# BSPD_v8.net
KiCad netlist of a schematic drawn in EAGLE
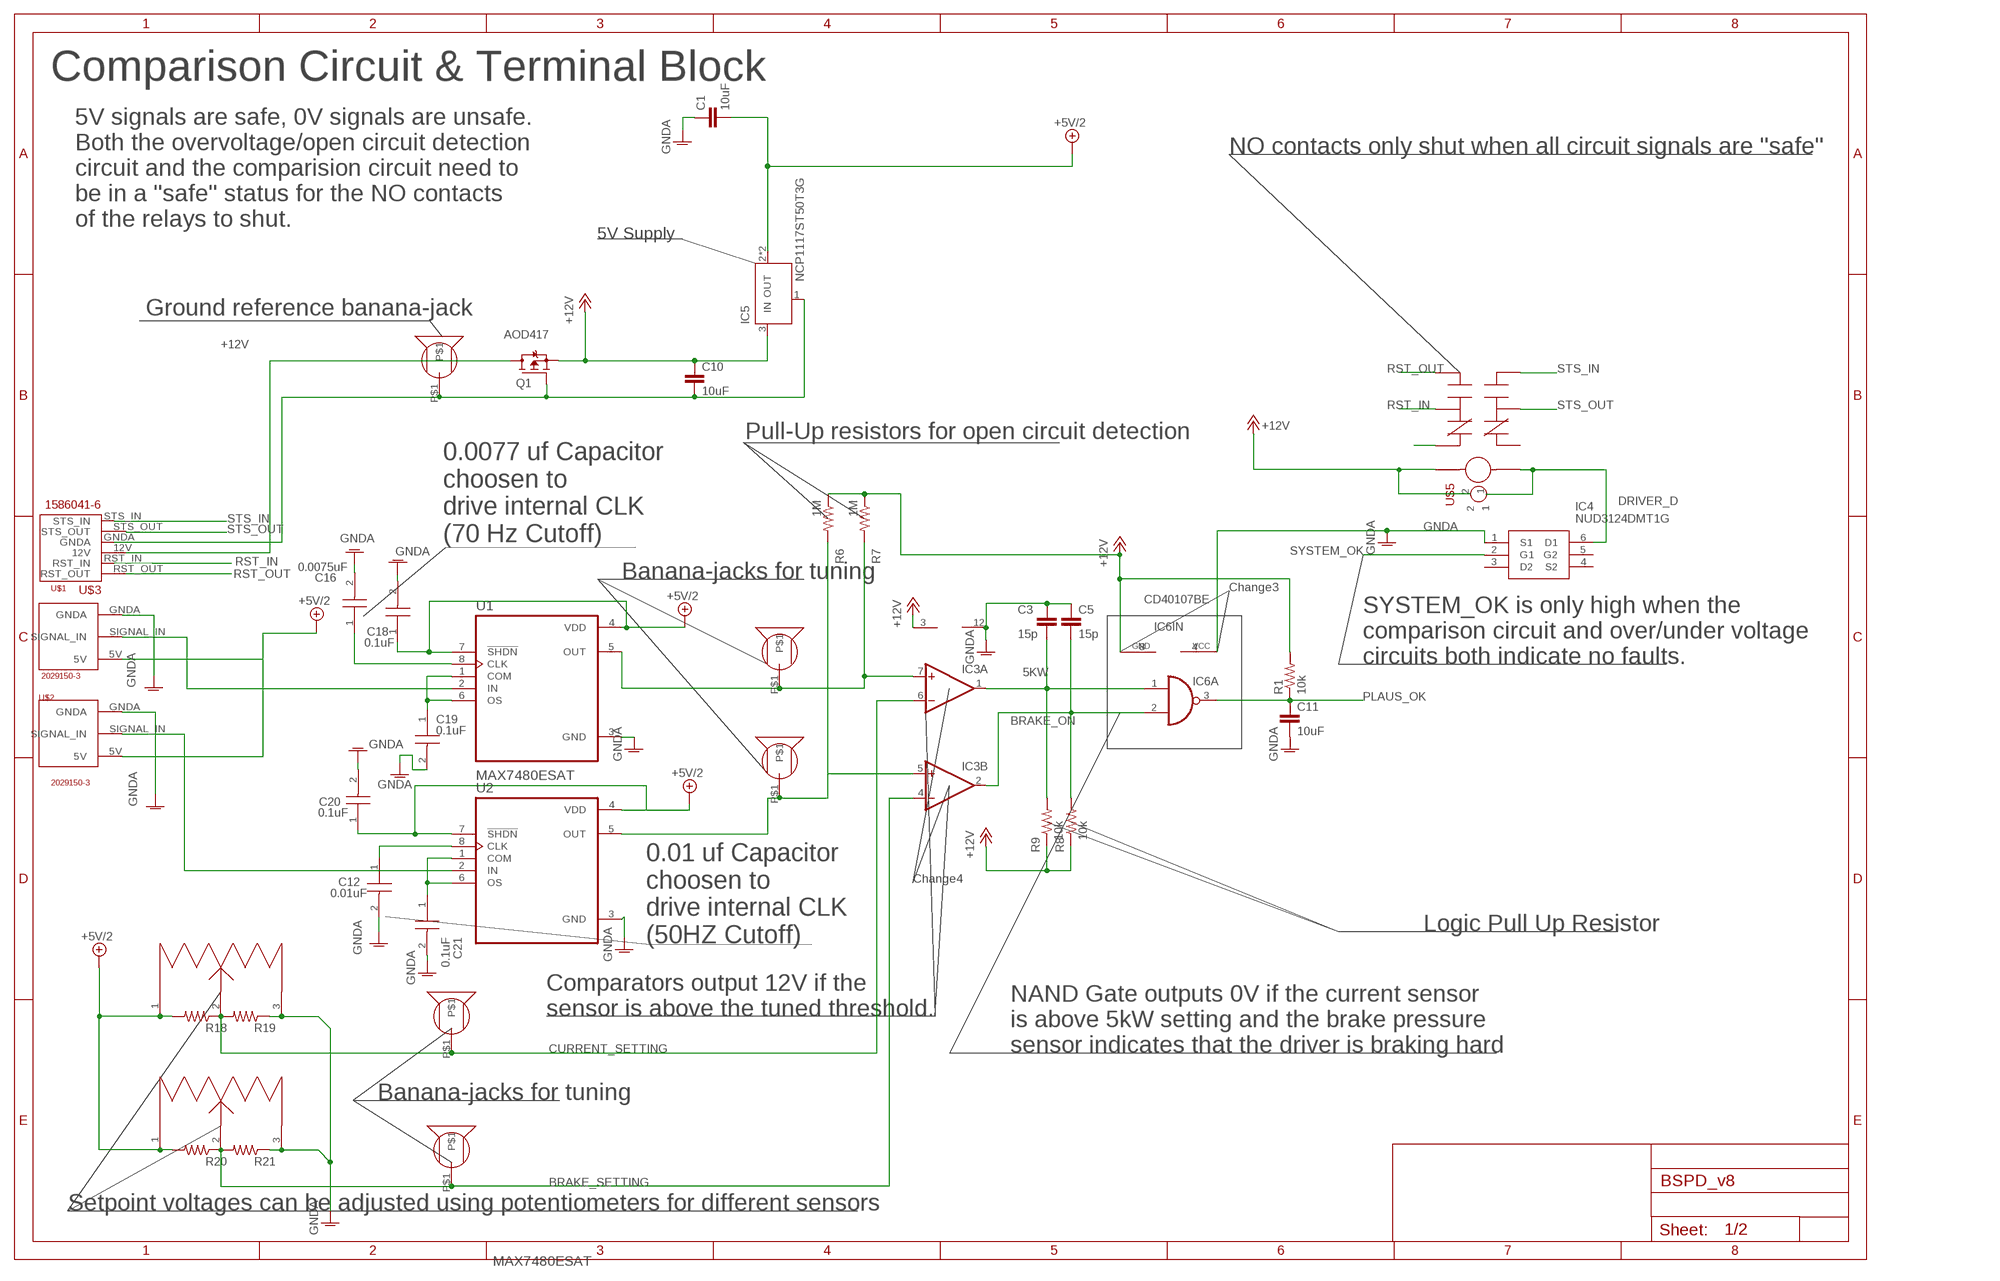
[diagram p0: schematic, sheet 1]
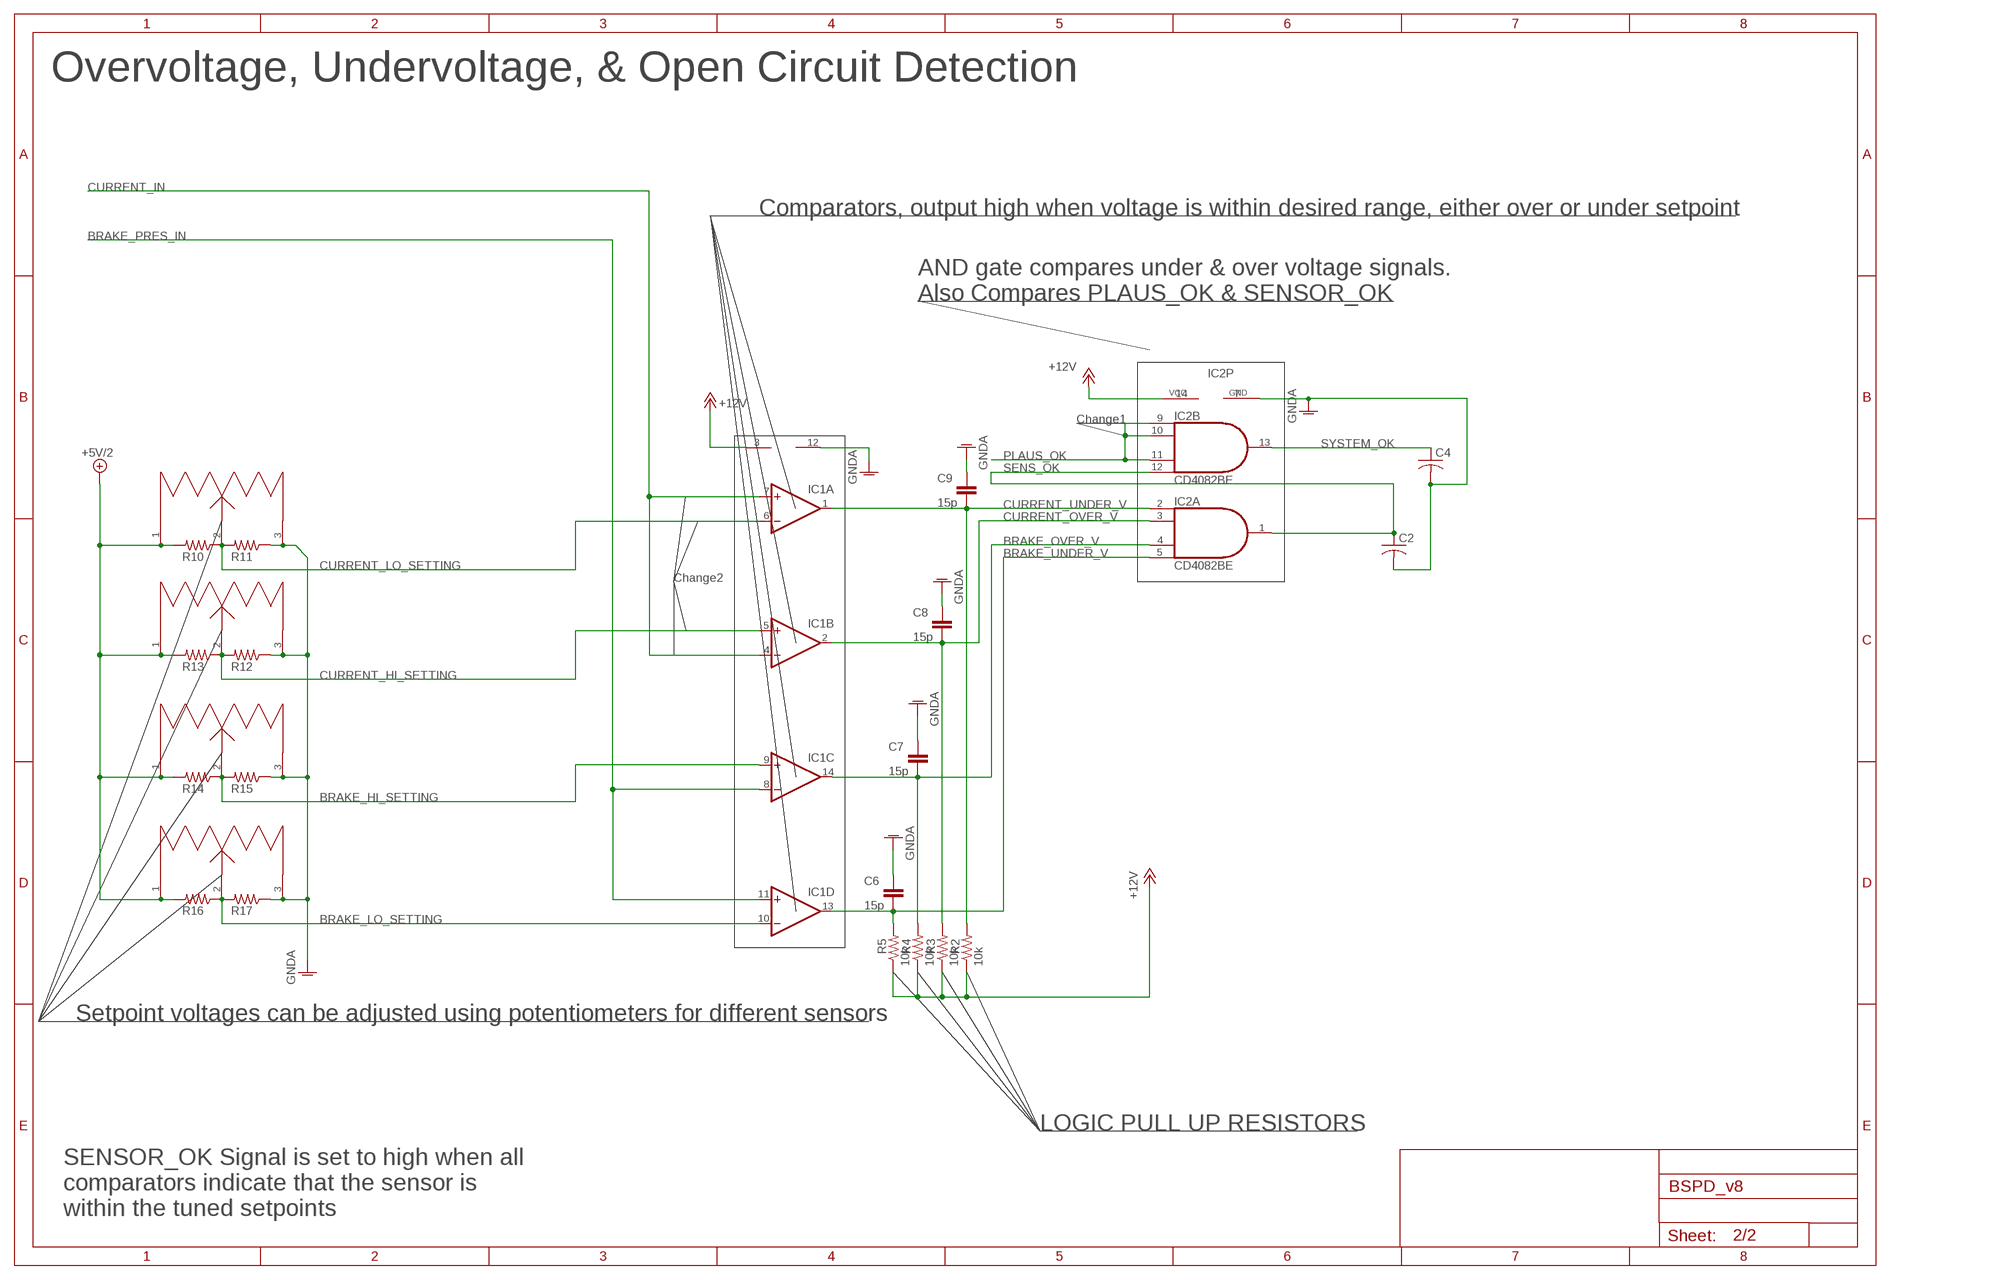
[diagram p1: schematic, sheet 2]

(export (version "E")
  (design (tool "Eeschema 10.0.6"))
  (components
    (comp (ref "C1")
      (value "10uF")
      (footprint "eagle-import:C0805")
      (libsource (lib "eagle-import") (part "resistor_348_C-EUC0805"))
    )
    (comp (ref "C3")
      (value "15p")
      (footprint "eagle-import:C0805")
      (libsource (lib "eagle-import") (part "C-EUC0805"))
    )
    (comp (ref "C5")
      (value "15p")
      (footprint "eagle-import:C0805")
      (libsource (lib "eagle-import") (part "C-EUC0805"))
    )
    (comp (ref "C10")
      (value "10uF")
      (footprint "eagle-import:C0805")
      (libsource (lib "eagle-import") (part "resistor_348_C-EUC0805"))
    )
    (comp (ref "C11")
      (value "10uF")
      (footprint "eagle-import:C0805")
      (libsource (lib "eagle-import") (part "resistor_348_C-EUC0805"))
    )
    (comp (ref "C12")
      (value "0.01uF")
      (footprint "eagle-import:CAPC2012X95N")
      (fields
        (field (name "MANUFACTURER_PART_NUMBER") "GRM2195C1H103JA01D")
        (field (name "MOUSER_PART_NUMBER") "81-GRM215C1H103JA01D")
      )
      (libsource (lib "eagle-import") (part "GRM2195C1H103JA01D"))
    )
    (comp (ref "C16")
      (value "0.0075uF")
      (footprint "eagle-import:CAPC2012X95N")
      (fields
        (field (name "MANUFACTURER_PART_NUMBER") "GRM2195C1H752JA01D")
        (field (name "MOUSER_PART_NUMBER") "81-GRM2195C1H752JA1D")
      )
      (libsource (lib "eagle-import") (part "GRM2195C1H752JA01D"))
    )
    (comp (ref "C18")
      (value "0.1uF")
      (footprint "eagle-import:CAPC2012X140N")
      (fields
        (field (name "MANUFACTURER_PART_NUMBER") "GCM21BR72A104KA37L")
        (field (name "MOUSER_PART_NUMBER") "81-GCM21BR72A104KA7L")
      )
      (libsource (lib "eagle-import") (part "GCM21BR72A104KA37L"))
    )
    (comp (ref "C19")
      (value "0.1uF")
      (footprint "eagle-import:CAPC2012X140N")
      (fields
        (field (name "MANUFACTURER_PART_NUMBER") "GCM21BR72A104KA37L")
        (field (name "MOUSER_PART_NUMBER") "81-GCM21BR72A104KA7L")
      )
      (libsource (lib "eagle-import") (part "GCM21BR72A104KA37L"))
    )
    (comp (ref "C20")
      (value "0.1uF")
      (footprint "eagle-import:CAPC2012X140N")
      (fields
        (field (name "MANUFACTURER_PART_NUMBER") "GCM21BR72A104KA37L")
        (field (name "MOUSER_PART_NUMBER") "81-GCM21BR72A104KA7L")
      )
      (libsource (lib "eagle-import") (part "GCM21BR72A104KA37L"))
    )
    (comp (ref "C21")
      (value "0.1uF")
      (footprint "eagle-import:CAPC2012X140N")
      (fields
        (field (name "MANUFACTURER_PART_NUMBER") "GCM21BR72A104KA37L")
        (field (name "MOUSER_PART_NUMBER") "81-GCM21BR72A104KA7L")
      )
      (libsource (lib "eagle-import") (part "GCM21BR72A104KA37L"))
    )
    (comp (ref "IC3")
      (value "4AMP_P11+7N")
      (footprint "eagle-import:DIL14")
      (libsource (lib "eagle-import") (part "4AMP_P11+7N"))
    )
    (comp (ref "IC4")
      (value "NUD3124DMT1G")
      (footprint "eagle-import:SOT95P275X110-6N")
      (fields (field (name "MOUSER_PART_NUMBER") "863-NUD3124DMT1G"))
      (libsource (lib "eagle-import") (part "NUD3124DMT1G"))
    )
    (comp (ref "IC5")
      (value "NCP1117ST50T3G")
      (footprint "eagle-import:SOT223")
      (libsource (lib "eagle-import") (part "NCP1117ST50T3G"))
    )
    (comp (ref "IC6")
      (value "CD40107BE")
      (footprint "eagle-import:DIL08")
      (libsource (lib "eagle-import") (part "CD40107BE"))
    )
    (comp (ref "Q1")
      (value "AOD417")
      (footprint "eagle-import:TO252")
      (fields (field (name "MF") "ON Semiconductor") (field (name "MP") "FDD4141"))
      (libsource (lib "eagle-import") (part "FDD4141TO252"))
    )
    (comp (ref "R1")
      (value "10k")
      (footprint "eagle-import:M0805")
      (libsource (lib "eagle-import") (part "R-US_M0805"))
    )
    (comp (ref "R6")
      (value "1M")
      (footprint "eagle-import:M0805")
      (libsource (lib "eagle-import") (part "resistor_R-US_M0805"))
    )
    (comp (ref "R7")
      (value "1M")
      (footprint "eagle-import:M0805")
      (libsource (lib "eagle-import") (part "resistor_R-US_M0805"))
    )
    (comp (ref "R8")
      (value "10k")
      (footprint "eagle-import:M0805")
      (libsource (lib "eagle-import") (part "resistor_R-US_M0805"))
    )
    (comp (ref "R9")
      (value "10k")
      (footprint "eagle-import:M0805")
      (libsource (lib "eagle-import") (part "resistor_R-US_M0805"))
    )
    (comp (ref "R18")
      (value "R-US_M0805")
      (footprint "eagle-import:M0805")
      (libsource (lib "eagle-import") (part "resistor_R-US_M0805"))
    )
    (comp (ref "R19")
      (value "R-US_M0805")
      (footprint "eagle-import:M0805")
      (libsource (lib "eagle-import") (part "resistor_R-US_M0805"))
    )
    (comp (ref "R20")
      (value "R-US_M0805")
      (footprint "eagle-import:M0805")
      (libsource (lib "eagle-import") (part "resistor_R-US_M0805"))
    )
    (comp (ref "R21")
      (value "R-US_M0805")
      (footprint "eagle-import:M0805")
      (libsource (lib "eagle-import") (part "resistor_R-US_M0805"))
    )
    (comp (ref "U$1")
      (value "2029150-3")
      (footprint "eagle-import:2029150-3")
      (libsource (lib "eagle-import") (part "2029150-3"))
    )
    (comp (ref "U$2")
      (value "2029150-3")
      (footprint "eagle-import:2029150-3")
      (libsource (lib "eagle-import") (part "2029150-3"))
    )
    (comp (ref "U$3")
      (value "1586041-6")
      (footprint "eagle-import:1586041-6")
      (libsource (lib "eagle-import") (part "1586041-6"))
    )
    (comp (ref "U$4")
      (value "BSPD_PARTS_MP_BANANA_PLUG")
      (footprint "eagle-import:BSPD_PARTS_BANANA_PLUG")
      (libsource (lib "eagle-import") (part "BSPD_PARTS_MP_BANANA_PLUG"))
    )
    (comp (ref "U$5")
      (value "SSL-LX3044ID-12V")
      (footprint "eagle-import:SSL-LX3044ID-12V")
      (libsource (lib "eagle-import") (part "SSL-LX3044ID-12V"))
    )
    (comp (ref "U$10")
      (value "PTC10LV10-103A1010")
      (footprint "eagle-import:PTC10LV10-103A1010")
      (libsource (lib "eagle-import") (part "PTC10LV10-103A1010"))
    )
    (comp (ref "U$11")
      (value "PTC10LV10-103A1010")
      (footprint "eagle-import:PTC10LV10-103A1010")
      (libsource (lib "eagle-import") (part "PTC10LV10-103A1010"))
    )
    (comp (ref "U$12")
      (value "BSPD_PARTS_RLY_V23079A1001B301")
      (footprint "eagle-import:BSPD_PARTS_V23079F1101B301")
      (libsource (lib "eagle-import") (part "BSPD_PARTS_RLY_V23079A1001B301"))
    )
    (comp (ref "U$13")
      (value "BSPD_PARTS_MP_BANANA_PLUG")
      (footprint "eagle-import:BSPD_PARTS_BANANA_PLUG")
      (libsource (lib "eagle-import") (part "BSPD_PARTS_MP_BANANA_PLUG"))
    )
    (comp (ref "U$14")
      (value "BSPD_PARTS_MP_BANANA_PLUG")
      (footprint "eagle-import:BSPD_PARTS_BANANA_PLUG")
      (libsource (lib "eagle-import") (part "BSPD_PARTS_MP_BANANA_PLUG"))
    )
    (comp (ref "U$18")
      (value "BSPD_PARTS_MP_BANANA_PLUG")
      (footprint "eagle-import:BSPD_PARTS_BANANA_PLUG")
      (libsource (lib "eagle-import") (part "BSPD_PARTS_MP_BANANA_PLUG"))
    )
    (comp (ref "U$19")
      (value "BSPD_PARTS_MP_BANANA_PLUG")
      (footprint "eagle-import:BSPD_PARTS_BANANA_PLUG")
      (libsource (lib "eagle-import") (part "BSPD_PARTS_MP_BANANA_PLUG"))
    )
    (comp (ref "U1")
      (value "MAX7480ESAT")
      (footprint "eagle-import:SOIC127P600X175-8N")
      (fields
        (field (name "DIGI-KEY_PART_NUMBER") "MAX7480ESA+-ND")
        (field (name "MF") "Maxim Integrated")
        (field (name "MP") "MAX7480ESA+")
      )
      (libsource (lib "eagle-import") (part "MAX7480ESAT"))
    )
    (comp (ref "U2")
      (value "MAX7480ESAT")
      (footprint "eagle-import:SOIC127P600X175-8N")
      (fields
        (field (name "DIGI-KEY_PART_NUMBER") "MAX7480ESA+-ND")
        (field (name "MF") "Maxim Integrated")
        (field (name "MP") "MAX7480ESA+")
      )
      (libsource (lib "eagle-import") (part "MAX7480ESAT"))
    )
    (comp (ref "C2")
      (value "C-USC0805")
      (footprint "eagle-import:C0805")
      (libsource (lib "eagle-import") (part "C-USC0805"))
    )
    (comp (ref "C4")
      (value "C-USC0805")
      (footprint "eagle-import:C0805")
      (libsource (lib "eagle-import") (part "C-USC0805"))
    )
    (comp (ref "C6")
      (value "15p")
      (footprint "eagle-import:C0805")
      (libsource (lib "eagle-import") (part "C-EUC0805"))
    )
    (comp (ref "C7")
      (value "15p")
      (footprint "eagle-import:C0805")
      (libsource (lib "eagle-import") (part "C-EUC0805"))
    )
    (comp (ref "C8")
      (value "15p")
      (footprint "eagle-import:C0805")
      (libsource (lib "eagle-import") (part "C-EUC0805"))
    )
    (comp (ref "C9")
      (value "15p")
      (footprint "eagle-import:C0805")
      (libsource (lib "eagle-import") (part "C-EUC0805"))
    )
    (comp (ref "IC1")
      (value "4AMP_P11+7N")
      (footprint "eagle-import:DIL14")
      (libsource (lib "eagle-import") (part "4AMP_P11+7N"))
    )
    (comp (ref "IC2")
      (value "CD4082BE")
      (footprint "eagle-import:DIL14")
      (libsource (lib "eagle-import") (part "7421NALS"))
    )
    (comp (ref "R2")
      (value "10k")
      (footprint "eagle-import:M0805")
      (libsource (lib "eagle-import") (part "resistor_R-US_M0805"))
    )
    (comp (ref "R3")
      (value "10k")
      (footprint "eagle-import:M0805")
      (libsource (lib "eagle-import") (part "resistor_R-US_M0805"))
    )
    (comp (ref "R4")
      (value "10k")
      (footprint "eagle-import:M0805")
      (libsource (lib "eagle-import") (part "resistor_R-US_M0805"))
    )
    (comp (ref "R5")
      (value "10k")
      (footprint "eagle-import:M0805")
      (libsource (lib "eagle-import") (part "resistor_R-US_M0805"))
    )
    (comp (ref "R10")
      (value "R-US_M0805")
      (footprint "eagle-import:M0805")
      (libsource (lib "eagle-import") (part "resistor_R-US_M0805"))
    )
    (comp (ref "R11")
      (value "R-US_M0805")
      (footprint "eagle-import:M0805")
      (libsource (lib "eagle-import") (part "resistor_R-US_M0805"))
    )
    (comp (ref "R12")
      (value "R-US_M0805")
      (footprint "eagle-import:M0805")
      (libsource (lib "eagle-import") (part "resistor_R-US_M0805"))
    )
    (comp (ref "R13")
      (value "R-US_M0805")
      (footprint "eagle-import:M0805")
      (libsource (lib "eagle-import") (part "resistor_R-US_M0805"))
    )
    (comp (ref "R14")
      (value "R-US_M0805")
      (footprint "eagle-import:M0805")
      (libsource (lib "eagle-import") (part "resistor_R-US_M0805"))
    )
    (comp (ref "R15")
      (value "R-US_M0805")
      (footprint "eagle-import:M0805")
      (libsource (lib "eagle-import") (part "resistor_R-US_M0805"))
    )
    (comp (ref "R16")
      (value "R-US_M0805")
      (footprint "eagle-import:M0805")
      (libsource (lib "eagle-import") (part "resistor_R-US_M0805"))
    )
    (comp (ref "R17")
      (value "R-US_M0805")
      (footprint "eagle-import:M0805")
      (libsource (lib "eagle-import") (part "resistor_R-US_M0805"))
    )
    (comp (ref "U$6")
      (value "PTC10LV10-103A1010")
      (footprint "eagle-import:PTC10LV10-103A1010")
      (libsource (lib "eagle-import") (part "PTC10LV10-103A1010"))
    )
    (comp (ref "U$7")
      (value "PTC10LV10-103A1010")
      (footprint "eagle-import:PTC10LV10-103A1010")
      (libsource (lib "eagle-import") (part "PTC10LV10-103A1010"))
    )
    (comp (ref "U$8")
      (value "PTC10LV10-103A1010")
      (footprint "eagle-import:PTC10LV10-103A1010")
      (libsource (lib "eagle-import") (part "PTC10LV10-103A1010"))
    )
    (comp (ref "U$9")
      (value "PTC10LV10-103A1010")
      (footprint "eagle-import:PTC10LV10-103A1010")
      (libsource (lib "eagle-import") (part "PTC10LV10-103A1010"))
    )
  )
  (nets
    (net (code "1") (name "+5V{slash}2") (class "Default")
      (node (ref "C1") (pin "2") (pinfunction "2_2") (pintype "passive"))
      (node (ref "C18") (pin "1") (pinfunction "1_1") (pintype "bidirectional"))
      (node (ref "C20") (pin "1") (pinfunction "1_1") (pintype "bidirectional"))
      (node (ref "IC5") (pin "2") (pinfunction "OUT_2") (pintype "passive"))
      (node (ref "IC5") (pin "4") (pinfunction "OUT_4") (pintype "passive"))
      (node (ref "R10") (pin "2") (pinfunction "2_2") (pintype "passive"))
      (node (ref "R13") (pin "2") (pinfunction "2_2") (pintype "passive"))
      (node (ref "R14") (pin "2") (pinfunction "2_2") (pintype "passive"))
      (node (ref "R16") (pin "2") (pinfunction "2_2") (pintype "passive"))
      (node (ref "R18") (pin "2") (pinfunction "2_2") (pintype "passive"))
      (node (ref "R20") (pin "2") (pinfunction "2_2") (pintype "passive"))
      (node (ref "U$1") (pin "5V") (pinfunction "5V_5V") (pintype "bidirectional"))
      (node (ref "U$10") (pin "1") (pinfunction "CW_1") (pintype "bidirectional"))
      (node (ref "U$11") (pin "1") (pinfunction "CW_1") (pintype "bidirectional"))
      (node (ref "U$2") (pin "5V") (pinfunction "5V_5V") (pintype "bidirectional"))
      (node (ref "U$6") (pin "1") (pinfunction "CW_1") (pintype "bidirectional"))
      (node (ref "U$7") (pin "1") (pinfunction "CW_1") (pintype "bidirectional"))
      (node (ref "U$8") (pin "1") (pinfunction "CW_1") (pintype "bidirectional"))
      (node (ref "U$9") (pin "1") (pinfunction "CW_1") (pintype "bidirectional"))
      (node (ref "U1") (pin "4") (pinfunction "VDD_4") (pintype "power_in"))
      (node (ref "U1") (pin "7") (pinfunction "~{SHDN}_7") (pintype "input"))
      (node (ref "U2") (pin "4") (pinfunction "VDD_4") (pintype "power_in"))
      (node (ref "U2") (pin "7") (pinfunction "~{SHDN}_7") (pintype "input"))
    )
    (net (code "2") (name "+12V") (class "Default")
      (node (ref "C10") (pin "1") (pinfunction "1_1") (pintype "passive"))
      (node (ref "IC1") (pin "3") (pinfunction "V+_3") (pintype "power_in"))
      (node (ref "IC2") (pin "14") (pinfunction "VCC_14") (pintype "power_in"))
      (node (ref "IC3") (pin "3") (pinfunction "V+_3") (pintype "power_in"))
      (node (ref "IC5") (pin "3") (pinfunction "IN_3") (pintype "input"))
      (node (ref "IC6") (pin "8") (pinfunction "GND_8") (pintype "power_in"))
      (node (ref "Q1") (pin "2") (pinfunction "S_2") (pintype "passive"))
      (node (ref "R1") (pin "2") (pinfunction "2_2") (pintype "passive"))
      (node (ref "R2") (pin "1") (pinfunction "1_1") (pintype "passive"))
      (node (ref "R3") (pin "1") (pinfunction "1_1") (pintype "passive"))
      (node (ref "R4") (pin "1") (pinfunction "1_1") (pintype "passive"))
      (node (ref "R5") (pin "1") (pinfunction "1_1") (pintype "passive"))
      (node (ref "R6") (pin "1") (pinfunction "1_1") (pintype "passive"))
      (node (ref "R7") (pin "1") (pinfunction "1_1") (pintype "passive"))
      (node (ref "R8") (pin "1") (pinfunction "1_1") (pintype "passive"))
      (node (ref "R9") (pin "1") (pinfunction "1_1") (pintype "passive"))
      (node (ref "U$12") (pin "1") (pinfunction "1_1") (pintype "bidirectional"))
      (node (ref "U$5") (pin "2") (pinfunction "2_2") (pintype "bidirectional"))
    )
    (net (code "3") (name "5KW") (class "Default")
      (node (ref "C3") (pin "2") (pinfunction "2_2") (pintype "passive"))
      (node (ref "IC3") (pin "1") (pinfunction "OUT_1") (pintype "output"))
      (node (ref "IC6") (pin "1") (pinfunction "I0_1") (pintype "input"))
      (node (ref "R9") (pin "2") (pinfunction "2_2") (pintype "passive"))
    )
    (net (code "4") (name "BRAKE_HI_SETTING") (class "Default")
      (node (ref "IC1") (pin "9") (pinfunction "+IN_9") (pintype "input"))
      (node (ref "R14") (pin "1") (pinfunction "1_1") (pintype "passive"))
      (node (ref "R15") (pin "2") (pinfunction "2_2") (pintype "passive"))
      (node (ref "U$8") (pin "2") (pinfunction "VO_2") (pintype "bidirectional"))
    )
    (net (code "5") (name "BRAKE_LO_SETTING") (class "Default")
      (node (ref "IC1") (pin "10") (pinfunction "-IN_10") (pintype "input"))
      (node (ref "R16") (pin "1") (pinfunction "1_1") (pintype "passive"))
      (node (ref "R17") (pin "2") (pinfunction "2_2") (pintype "passive"))
      (node (ref "U$9") (pin "2") (pinfunction "VO_2") (pintype "bidirectional"))
    )
    (net (code "6") (name "BRAKE_ON") (class "Default")
      (node (ref "C5") (pin "2") (pinfunction "2_2") (pintype "passive"))
      (node (ref "IC3") (pin "2") (pinfunction "OUT_2") (pintype "output"))
      (node (ref "IC6") (pin "2") (pinfunction "I1_2") (pintype "input"))
      (node (ref "R8") (pin "2") (pinfunction "2_2") (pintype "passive"))
    )
    (net (code "7") (name "BRAKE_OVER_V") (class "Default")
      (node (ref "C7") (pin "2") (pinfunction "2_2") (pintype "passive"))
      (node (ref "IC1") (pin "14") (pinfunction "OUT_14") (pintype "output"))
      (node (ref "IC2") (pin "4") (pinfunction "I2_4") (pintype "input"))
      (node (ref "R4") (pin "2") (pinfunction "2_2") (pintype "passive"))
    )
    (net (code "8") (name "BRAKE_PRES_IN") (class "Default")
      (node (ref "IC1") (pin "11") (pinfunction "+IN_11") (pintype "input"))
      (node (ref "IC1") (pin "8") (pinfunction "-IN_8") (pintype "input"))
      (node (ref "IC3") (pin "5") (pinfunction "+IN_5") (pintype "input"))
      (node (ref "R6") (pin "2") (pinfunction "2_2") (pintype "passive"))
      (node (ref "U$14") (pin "P$1") (pinfunction "P$1_P$1") (pintype "bidirectional"))
      (node (ref "U2") (pin "5") (pinfunction "OUT_5") (pintype "output"))
    )
    (net (code "9") (name "BRAKE_SETTING") (class "Default")
      (node (ref "IC3") (pin "4") (pinfunction "-IN_4") (pintype "input"))
      (node (ref "R20") (pin "1") (pinfunction "1_1") (pintype "passive"))
      (node (ref "R21") (pin "2") (pinfunction "2_2") (pintype "passive"))
      (node (ref "U$10") (pin "2") (pinfunction "VO_2") (pintype "bidirectional"))
      (node (ref "U$19") (pin "P$1") (pinfunction "P$1_P$1") (pintype "bidirectional"))
    )
    (net (code "10") (name "BRAKE_UNDER_V") (class "Default")
      (node (ref "C6") (pin "2") (pinfunction "2_2") (pintype "passive"))
      (node (ref "IC1") (pin "13") (pinfunction "OUT_13") (pintype "output"))
      (node (ref "IC2") (pin "5") (pinfunction "I3_5") (pintype "input"))
      (node (ref "R5") (pin "2") (pinfunction "2_2") (pintype "passive"))
    )
    (net (code "11") (name "CURRENT_HI_SETTING") (class "Default")
      (node (ref "IC1") (pin "5") (pinfunction "+IN_5") (pintype "input"))
      (node (ref "R12") (pin "2") (pinfunction "2_2") (pintype "passive"))
      (node (ref "R13") (pin "1") (pinfunction "1_1") (pintype "passive"))
      (node (ref "U$7") (pin "2") (pinfunction "VO_2") (pintype "bidirectional"))
    )
    (net (code "12") (name "CURRENT_IN") (class "Default")
      (node (ref "IC1") (pin "4") (pinfunction "-IN_4") (pintype "input"))
      (node (ref "IC1") (pin "7") (pinfunction "+IN_7") (pintype "input"))
      (node (ref "IC3") (pin "7") (pinfunction "+IN_7") (pintype "input"))
      (node (ref "R7") (pin "2") (pinfunction "2_2") (pintype "passive"))
      (node (ref "U$13") (pin "P$1") (pinfunction "P$1_P$1") (pintype "bidirectional"))
      (node (ref "U1") (pin "5") (pinfunction "OUT_5") (pintype "output"))
    )
    (net (code "13") (name "CURRENT_LO_SETTING") (class "Default")
      (node (ref "IC1") (pin "6") (pinfunction "-IN_6") (pintype "input"))
      (node (ref "R10") (pin "1") (pinfunction "1_1") (pintype "passive"))
      (node (ref "R11") (pin "2") (pinfunction "2_2") (pintype "passive"))
      (node (ref "U$6") (pin "2") (pinfunction "VO_2") (pintype "bidirectional"))
    )
    (net (code "14") (name "CURRENT_OVER_V") (class "Default")
      (node (ref "C8") (pin "2") (pinfunction "2_2") (pintype "passive"))
      (node (ref "IC1") (pin "2") (pinfunction "OUT_2") (pintype "output"))
      (node (ref "IC2") (pin "3") (pinfunction "I1_3") (pintype "input"))
      (node (ref "R3") (pin "2") (pinfunction "2_2") (pintype "passive"))
    )
    (net (code "15") (name "CURRENT_SETTING") (class "Default")
      (node (ref "IC3") (pin "6") (pinfunction "-IN_6") (pintype "input"))
      (node (ref "R18") (pin "1") (pinfunction "1_1") (pintype "passive"))
      (node (ref "R19") (pin "2") (pinfunction "2_2") (pintype "passive"))
      (node (ref "U$11") (pin "2") (pinfunction "VO_2") (pintype "bidirectional"))
      (node (ref "U$18") (pin "P$1") (pinfunction "P$1_P$1") (pintype "bidirectional"))
    )
    (net (code "16") (name "CURRENT_UNDER_V") (class "Default")
      (node (ref "C9") (pin "2") (pinfunction "2_2") (pintype "passive"))
      (node (ref "IC1") (pin "1") (pinfunction "OUT_1") (pintype "output"))
      (node (ref "IC2") (pin "2") (pinfunction "I0_2") (pintype "input"))
      (node (ref "R2") (pin "2") (pinfunction "2_2") (pintype "passive"))
    )
    (net (code "17") (name "DRIVER_D") (class "Default")
      (node (ref "IC4") (pin "6") (pinfunction "D1_6") (pintype "bidirectional"))
      (node (ref "U$12") (pin "12") (pinfunction "12_12") (pintype "bidirectional"))
      (node (ref "U$5") (pin "1") (pinfunction "1_1") (pintype "bidirectional"))
    )
    (net (code "18") (name "GNDA") (class "Default")
      (node (ref "C1") (pin "1") (pinfunction "1_1") (pintype "passive"))
      (node (ref "C10") (pin "2") (pinfunction "2_2") (pintype "passive"))
      (node (ref "C11") (pin "2") (pinfunction "2_2") (pintype "passive"))
      (node (ref "C12") (pin "2") (pinfunction "2_2") (pintype "bidirectional"))
      (node (ref "C16") (pin "2") (pinfunction "2_2") (pintype "bidirectional"))
      (node (ref "C18") (pin "2") (pinfunction "2_2") (pintype "bidirectional"))
      (node (ref "C19") (pin "2") (pinfunction "2_2") (pintype "bidirectional"))
      (node (ref "C2") (pin "2") (pinfunction "2_2") (pintype "passive"))
      (node (ref "C20") (pin "2") (pinfunction "2_2") (pintype "bidirectional"))
      (node (ref "C21") (pin "2") (pinfunction "2_2") (pintype "bidirectional"))
      (node (ref "C3") (pin "1") (pinfunction "1_1") (pintype "passive"))
      (node (ref "C4") (pin "2") (pinfunction "2_2") (pintype "passive"))
      (node (ref "C5") (pin "1") (pinfunction "1_1") (pintype "passive"))
      (node (ref "C6") (pin "1") (pinfunction "1_1") (pintype "passive"))
      (node (ref "C7") (pin "1") (pinfunction "1_1") (pintype "passive"))
      (node (ref "C8") (pin "1") (pinfunction "1_1") (pintype "passive"))
      (node (ref "C9") (pin "1") (pinfunction "1_1") (pintype "passive"))
      (node (ref "IC1") (pin "12") (pinfunction "V-_12") (pintype "power_in"))
      (node (ref "IC2") (pin "7") (pinfunction "GND_7") (pintype "power_in"))
      (node (ref "IC3") (pin "12") (pinfunction "V-_12") (pintype "power_in"))
      (node (ref "IC4") (pin "1") (pinfunction "S1_1") (pintype "bidirectional"))
      (node (ref "IC5") (pin "1") (pinfunction "GND_1") (pintype "power_in"))
      (node (ref "IC6") (pin "4") (pinfunction "VCC_4") (pintype "power_in"))
      (node (ref "Q1") (pin "1") (pinfunction "G_1") (pintype "passive"))
      (node (ref "R11") (pin "1") (pinfunction "1_1") (pintype "passive"))
      (node (ref "R12") (pin "1") (pinfunction "1_1") (pintype "passive"))
      (node (ref "R15") (pin "1") (pinfunction "1_1") (pintype "passive"))
      (node (ref "R17") (pin "1") (pinfunction "1_1") (pintype "passive"))
      (node (ref "R19") (pin "1") (pinfunction "1_1") (pintype "passive"))
      (node (ref "R21") (pin "1") (pinfunction "1_1") (pintype "passive"))
      (node (ref "U$1") (pin "GNDA") (pinfunction "GNDA_GNDA") (pintype "bidirectional"))
      (node (ref "U$10") (pin "3") (pinfunction "CCW_3") (pintype "bidirectional"))
      (node (ref "U$11") (pin "3") (pinfunction "CCW_3") (pintype "bidirectional"))
      (node (ref "U$2") (pin "GNDA") (pinfunction "GNDA_GNDA") (pintype "bidirectional"))
      (node (ref "U$3") (pin "GNDA") (pinfunction "GNDA_GNDA") (pintype "bidirectional"))
      (node (ref "U$4") (pin "P$1") (pinfunction "P$1_P$1") (pintype "bidirectional"))
      (node (ref "U$6") (pin "3") (pinfunction "CCW_3") (pintype "bidirectional"))
      (node (ref "U$7") (pin "3") (pinfunction "CCW_3") (pintype "bidirectional"))
      (node (ref "U$8") (pin "3") (pinfunction "CCW_3") (pintype "bidirectional"))
      (node (ref "U$9") (pin "3") (pinfunction "CCW_3") (pintype "bidirectional"))
      (node (ref "U1") (pin "3") (pinfunction "GND_3") (pintype "power_in"))
      (node (ref "U2") (pin "3") (pinfunction "GND_3") (pintype "power_in"))
    )
    (net (code "19") (name "Net-(Q1-D)") (class "Default")
      (node (ref "Q1") (pin "3") (pinfunction "D_3") (pintype "passive"))
      (node (ref "U$3") (pin "12V") (pinfunction "12V_12V") (pintype "bidirectional"))
    )
    (net (code "20") (name "Net-(U1-CLK)") (class "Default")
      (node (ref "C16") (pin "1") (pinfunction "1_1") (pintype "bidirectional"))
      (node (ref "U1") (pin "8") (pinfunction "CLK_8") (pintype "input"))
    )
    (net (code "21") (name "Net-(U1-COM)") (class "Default")
      (node (ref "C19") (pin "1") (pinfunction "1_1") (pintype "bidirectional"))
      (node (ref "U1") (pin "1") (pinfunction "COM_1") (pintype "input"))
      (node (ref "U1") (pin "6") (pinfunction "OS_6") (pintype "input"))
    )
    (net (code "22") (name "Net-(U1-IN)") (class "Default")
      (node (ref "U$1") (pin "SIGNAL_IN") (pinfunction "SIGNAL_IN_SIGNAL_IN") (pintype "bidirectional"))
      (node (ref "U1") (pin "2") (pinfunction "IN_2") (pintype "input"))
    )
    (net (code "23") (name "Net-(U2-CLK)") (class "Default")
      (node (ref "C12") (pin "1") (pinfunction "1_1") (pintype "bidirectional"))
      (node (ref "U2") (pin "8") (pinfunction "CLK_8") (pintype "input"))
    )
    (net (code "24") (name "Net-(U2-COM)") (class "Default")
      (node (ref "C21") (pin "1") (pinfunction "1_1") (pintype "bidirectional"))
      (node (ref "U2") (pin "1") (pinfunction "COM_1") (pintype "input"))
      (node (ref "U2") (pin "6") (pinfunction "OS_6") (pintype "input"))
    )
    (net (code "25") (name "Net-(U2-IN)") (class "Default")
      (node (ref "U$2") (pin "SIGNAL_IN") (pinfunction "SIGNAL_IN_SIGNAL_IN") (pintype "bidirectional"))
      (node (ref "U2") (pin "2") (pinfunction "IN_2") (pintype "input"))
    )
    (net (code "26") (name "PLAUS_OK") (class "Default")
      (node (ref "C11") (pin "1") (pinfunction "1_1") (pintype "passive"))
      (node (ref "IC2") (pin "10") (pinfunction "I1_10") (pintype "input"))
      (node (ref "IC2") (pin "11") (pinfunction "I2_11") (pintype "input"))
      (node (ref "IC2") (pin "9") (pinfunction "I0_9") (pintype "input"))
      (node (ref "IC6") (pin "3") (pinfunction "O_3") (pintype "output"))
      (node (ref "R1") (pin "1") (pinfunction "1_1") (pintype "passive"))
    )
    (net (code "27") (name "RST_IN") (class "Default")
      (node (ref "U$12") (pin "4") (pinfunction "4_4") (pintype "bidirectional"))
      (node (ref "U$3") (pin "RST_IN") (pinfunction "RST_IN_RST_IN") (pintype "bidirectional"))
    )
    (net (code "28") (name "RST_OUT") (class "Default")
      (node (ref "U$12") (pin "5") (pinfunction "5_5") (pintype "bidirectional"))
      (node (ref "U$3") (pin "RST_OUT") (pinfunction "RST_OUT_RST_OUT") (pintype "bidirectional"))
    )
    (net (code "29") (name "SENS_OK") (class "Default")
      (node (ref "C2") (pin "1") (pinfunction "1_1") (pintype "passive"))
      (node (ref "IC2") (pin "1") (pinfunction "O_1") (pintype "output"))
      (node (ref "IC2") (pin "12") (pinfunction "I3_12") (pintype "input"))
    )
    (net (code "30") (name "STS_IN") (class "Default")
      (node (ref "U$12") (pin "8") (pinfunction "8_8") (pintype "bidirectional"))
      (node (ref "U$3") (pin "STS_IN") (pinfunction "STS_IN_STS_IN") (pintype "bidirectional"))
    )
    (net (code "31") (name "STS_OUT") (class "Default")
      (node (ref "U$12") (pin "9") (pinfunction "9_9") (pintype "bidirectional"))
      (node (ref "U$3") (pin "STS_OUT") (pinfunction "STS_OUT_STS_OUT") (pintype "bidirectional"))
    )
    (net (code "32") (name "SYSTEM_OK") (class "Default")
      (node (ref "C4") (pin "1") (pinfunction "1_1") (pintype "passive"))
      (node (ref "IC2") (pin "13") (pinfunction "O_13") (pintype "output"))
      (node (ref "IC4") (pin "2") (pinfunction "G1_2") (pintype "bidirectional"))
    )
    (net (code "33") (name "unconnected-(IC4-D2-Pad3)") (class "Default")
      (node (ref "IC4") (pin "3") (pinfunction "D2_3") (pintype "bidirectional"))
    )
    (net (code "34") (name "unconnected-(IC4-G2-Pad5)") (class "Default")
      (node (ref "IC4") (pin "5") (pinfunction "G2_5") (pintype "bidirectional"))
    )
    (net (code "35") (name "unconnected-(IC4-S2-Pad4)") (class "Default")
      (node (ref "IC4") (pin "4") (pinfunction "S2_4") (pintype "bidirectional"))
    )
    (net (code "36") (name "unconnected-(U$12-Pad3)") (class "Default")
      (node (ref "U$12") (pin "3") (pinfunction "3_3") (pintype "bidirectional"))
    )
    (net (code "37") (name "unconnected-(U$12-Pad10)") (class "Default")
      (node (ref "U$12") (pin "10") (pinfunction "10_10") (pintype "bidirectional"))
    )
  )
)
